# imu-pcb.net
KiCad netlist of a schematic drawn in Altium Designer
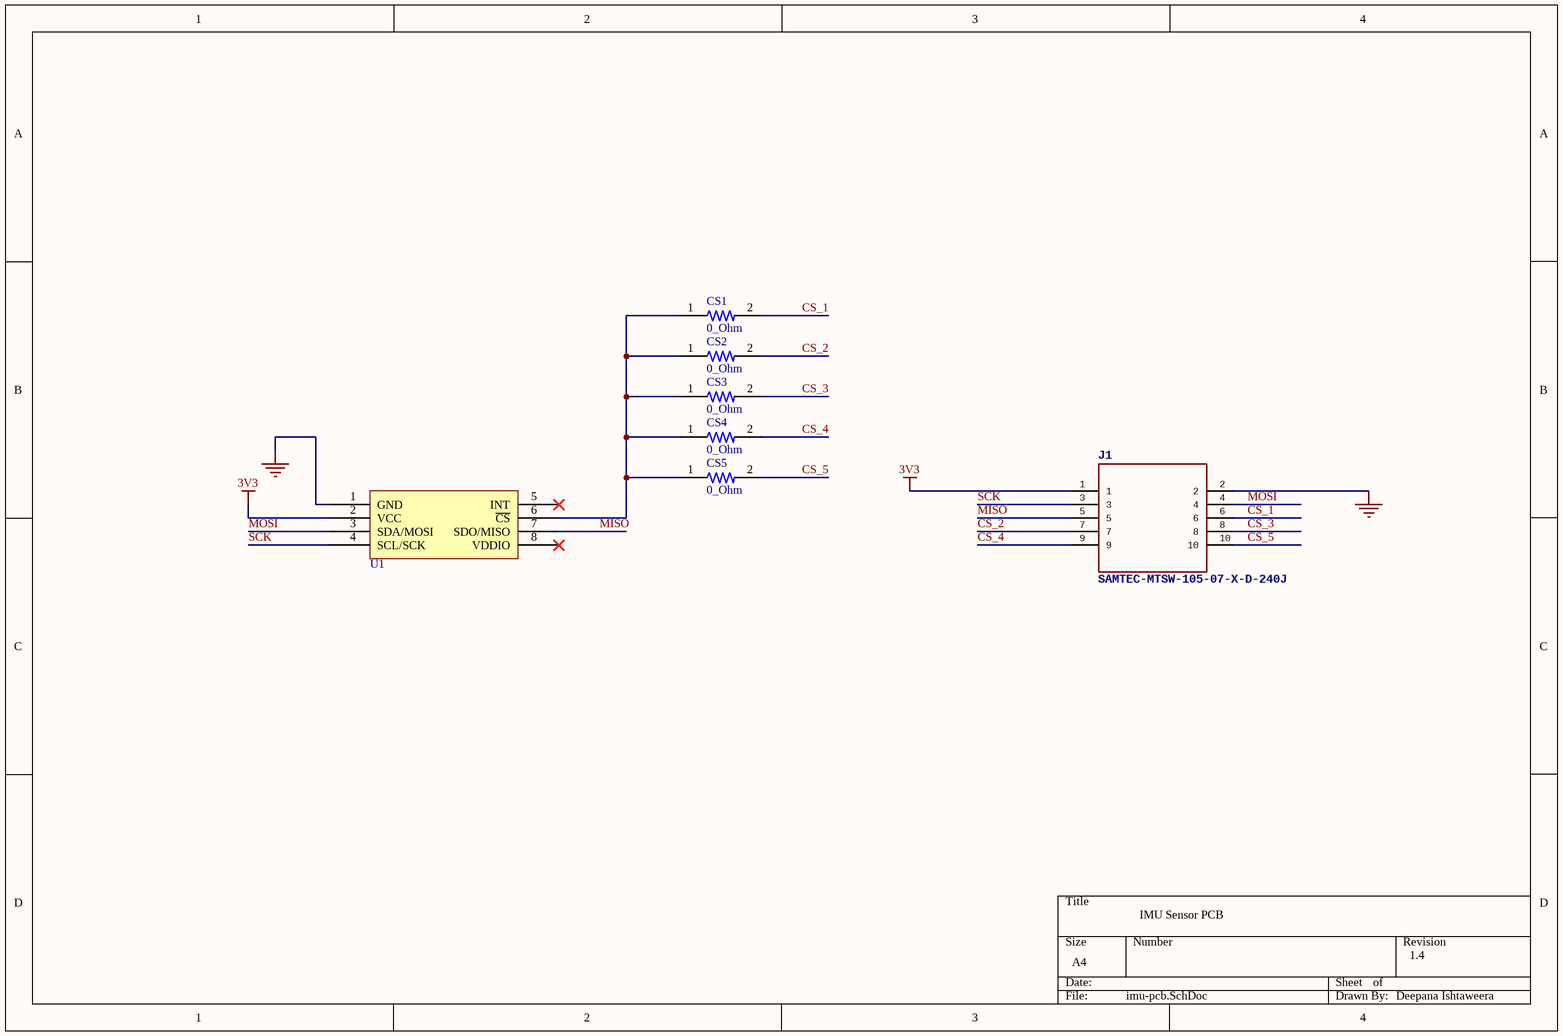
[diagram p0: imu-pcb.SchDoc]

(export (version "E")
  (design (tool "Eeschema 10.0.6"))
  (components
    (comp (ref "CS1")
      (value "0_Ohm")
      (footprint "RESC1608X50N")
      (description "RES SMD 10 OHM 0.1% 1/16W 0603")
      (fields (field (name "MF") "TE Connectivity") (field (name "MP") "8-1614350-7"))
      (libsource (lib "imu-pcb-lib") (part "RES-0603_0"))
    )
    (comp (ref "CS2")
      (value "0_Ohm")
      (footprint "RESC1608X50N")
      (description "RES SMD 10 OHM 0.1% 1/16W 0603")
      (fields (field (name "MF") "TE Connectivity") (field (name "MP") "8-1614350-7"))
      (libsource (lib "imu-pcb-lib") (part "RES-0603_0"))
    )
    (comp (ref "CS3")
      (value "0_Ohm")
      (footprint "RESC1608X50N")
      (description "RES SMD 10 OHM 0.1% 1/16W 0603")
      (fields (field (name "MF") "TE Connectivity") (field (name "MP") "8-1614350-7"))
      (libsource (lib "imu-pcb-lib") (part "RES-0603_0"))
    )
    (comp (ref "CS4")
      (value "0_Ohm")
      (footprint "RESC1608X50N")
      (description "RES SMD 10 OHM 0.1% 1/16W 0603")
      (fields (field (name "MF") "TE Connectivity") (field (name "MP") "8-1614350-7"))
      (libsource (lib "imu-pcb-lib") (part "RES-0603_0"))
    )
    (comp (ref "CS5")
      (value "0_Ohm")
      (footprint "RESC1608X50N")
      (description "RES SMD 10 OHM 0.1% 1/16W 0603")
      (fields (field (name "MF") "TE Connectivity") (field (name "MP") "8-1614350-7"))
      (libsource (lib "imu-pcb-lib") (part "RES-0603_0"))
    )
    (comp (ref "J1")
      (value "SAMTEC-MTSW-105-07-X-D-240J")
      (footprint "IDC_2.54_10")
      (description "5x2 male connector (2.54mm)")
      (libsource (lib "imu-pcb-lib") (part "IDC_2.54mm_10pos"))
    )
    (comp (ref "U1")
      (value "Sparkfun_MPU9250")
      (footprint "Sparkfun_MPU9250")
      (description "https://learn.sparkfun.com/tutorials/mpu-9250-hookup-guide/all#resources-and-going-further")
      (libsource (lib "imu-pcb-lib") (part "Sparkfun_MPU9250"))
    )
  )
  (nets
    (net (code "1") (name "/CS_1") (class "Default")
      (node (ref "CS1") (pin "2") (pinfunction "2_2") (pintype "passive"))
      (node (ref "J1") (pin "6") (pinfunction "6_6") (pintype "passive"))
    )
    (net (code "2") (name "/CS_2") (class "Default")
      (node (ref "CS2") (pin "2") (pinfunction "2_2") (pintype "passive"))
      (node (ref "J1") (pin "7") (pinfunction "7_7") (pintype "passive"))
    )
    (net (code "3") (name "/CS_3") (class "Default")
      (node (ref "CS3") (pin "2") (pinfunction "2_2") (pintype "passive"))
      (node (ref "J1") (pin "8") (pinfunction "8_8") (pintype "passive"))
    )
    (net (code "4") (name "/CS_4") (class "Default")
      (node (ref "CS4") (pin "2") (pinfunction "2_2") (pintype "passive"))
      (node (ref "J1") (pin "9") (pinfunction "9_9") (pintype "passive"))
    )
    (net (code "5") (name "/CS_5") (class "Default")
      (node (ref "CS5") (pin "2") (pinfunction "2_2") (pintype "passive"))
      (node (ref "J1") (pin "10") (pinfunction "10_10") (pintype "passive"))
    )
    (net (code "6") (name "/MISO") (class "Default")
      (node (ref "J1") (pin "5") (pinfunction "5_5") (pintype "passive"))
      (node (ref "U1") (pin "7") (pinfunction "SDO/MISO_7") (pintype "passive"))
    )
    (net (code "7") (name "/MOSI") (class "Default")
      (node (ref "J1") (pin "4") (pinfunction "4_4") (pintype "passive"))
      (node (ref "U1") (pin "3") (pinfunction "SDA/MOSI_3") (pintype "passive"))
    )
    (net (code "8") (name "/SCK") (class "Default")
      (node (ref "J1") (pin "3") (pinfunction "3_3") (pintype "passive"))
      (node (ref "U1") (pin "4") (pinfunction "SCL/SCK_4") (pintype "passive"))
    )
    (net (code "9") (name "3V3") (class "Default")
      (node (ref "J1") (pin "1") (pinfunction "1_1") (pintype "passive"))
      (node (ref "U1") (pin "2") (pinfunction "VCC_2") (pintype "passive"))
    )
    (net (code "10") (name "GND") (class "Default")
      (node (ref "J1") (pin "2") (pinfunction "2_2") (pintype "passive"))
      (node (ref "U1") (pin "1") (pinfunction "GND_1") (pintype "passive"))
    )
    (net (code "11") (name "Net-(U1-~{CS})") (class "Default")
      (node (ref "CS1") (pin "1") (pinfunction "1_1") (pintype "passive"))
      (node (ref "CS2") (pin "1") (pinfunction "1_1") (pintype "passive"))
      (node (ref "CS3") (pin "1") (pinfunction "1_1") (pintype "passive"))
      (node (ref "CS4") (pin "1") (pinfunction "1_1") (pintype "passive"))
      (node (ref "CS5") (pin "1") (pinfunction "1_1") (pintype "passive"))
      (node (ref "U1") (pin "6") (pinfunction "~{CS}_6") (pintype "passive"))
    )
    (net (code "12") (name "unconnected-(U1-INT-Pad5)") (class "Default")
      (node (ref "U1") (pin "5") (pinfunction "INT_5") (pintype "passive+no_connect"))
    )
    (net (code "13") (name "unconnected-(U1-VDDIO-Pad8)") (class "Default")
      (node (ref "U1") (pin "8") (pinfunction "VDDIO_8") (pintype "passive+no_connect"))
    )
  )
)
